# SimpleSwitchPirLightCO2_ESP03.net
KiCad netlist of a schematic drawn in EAGLE
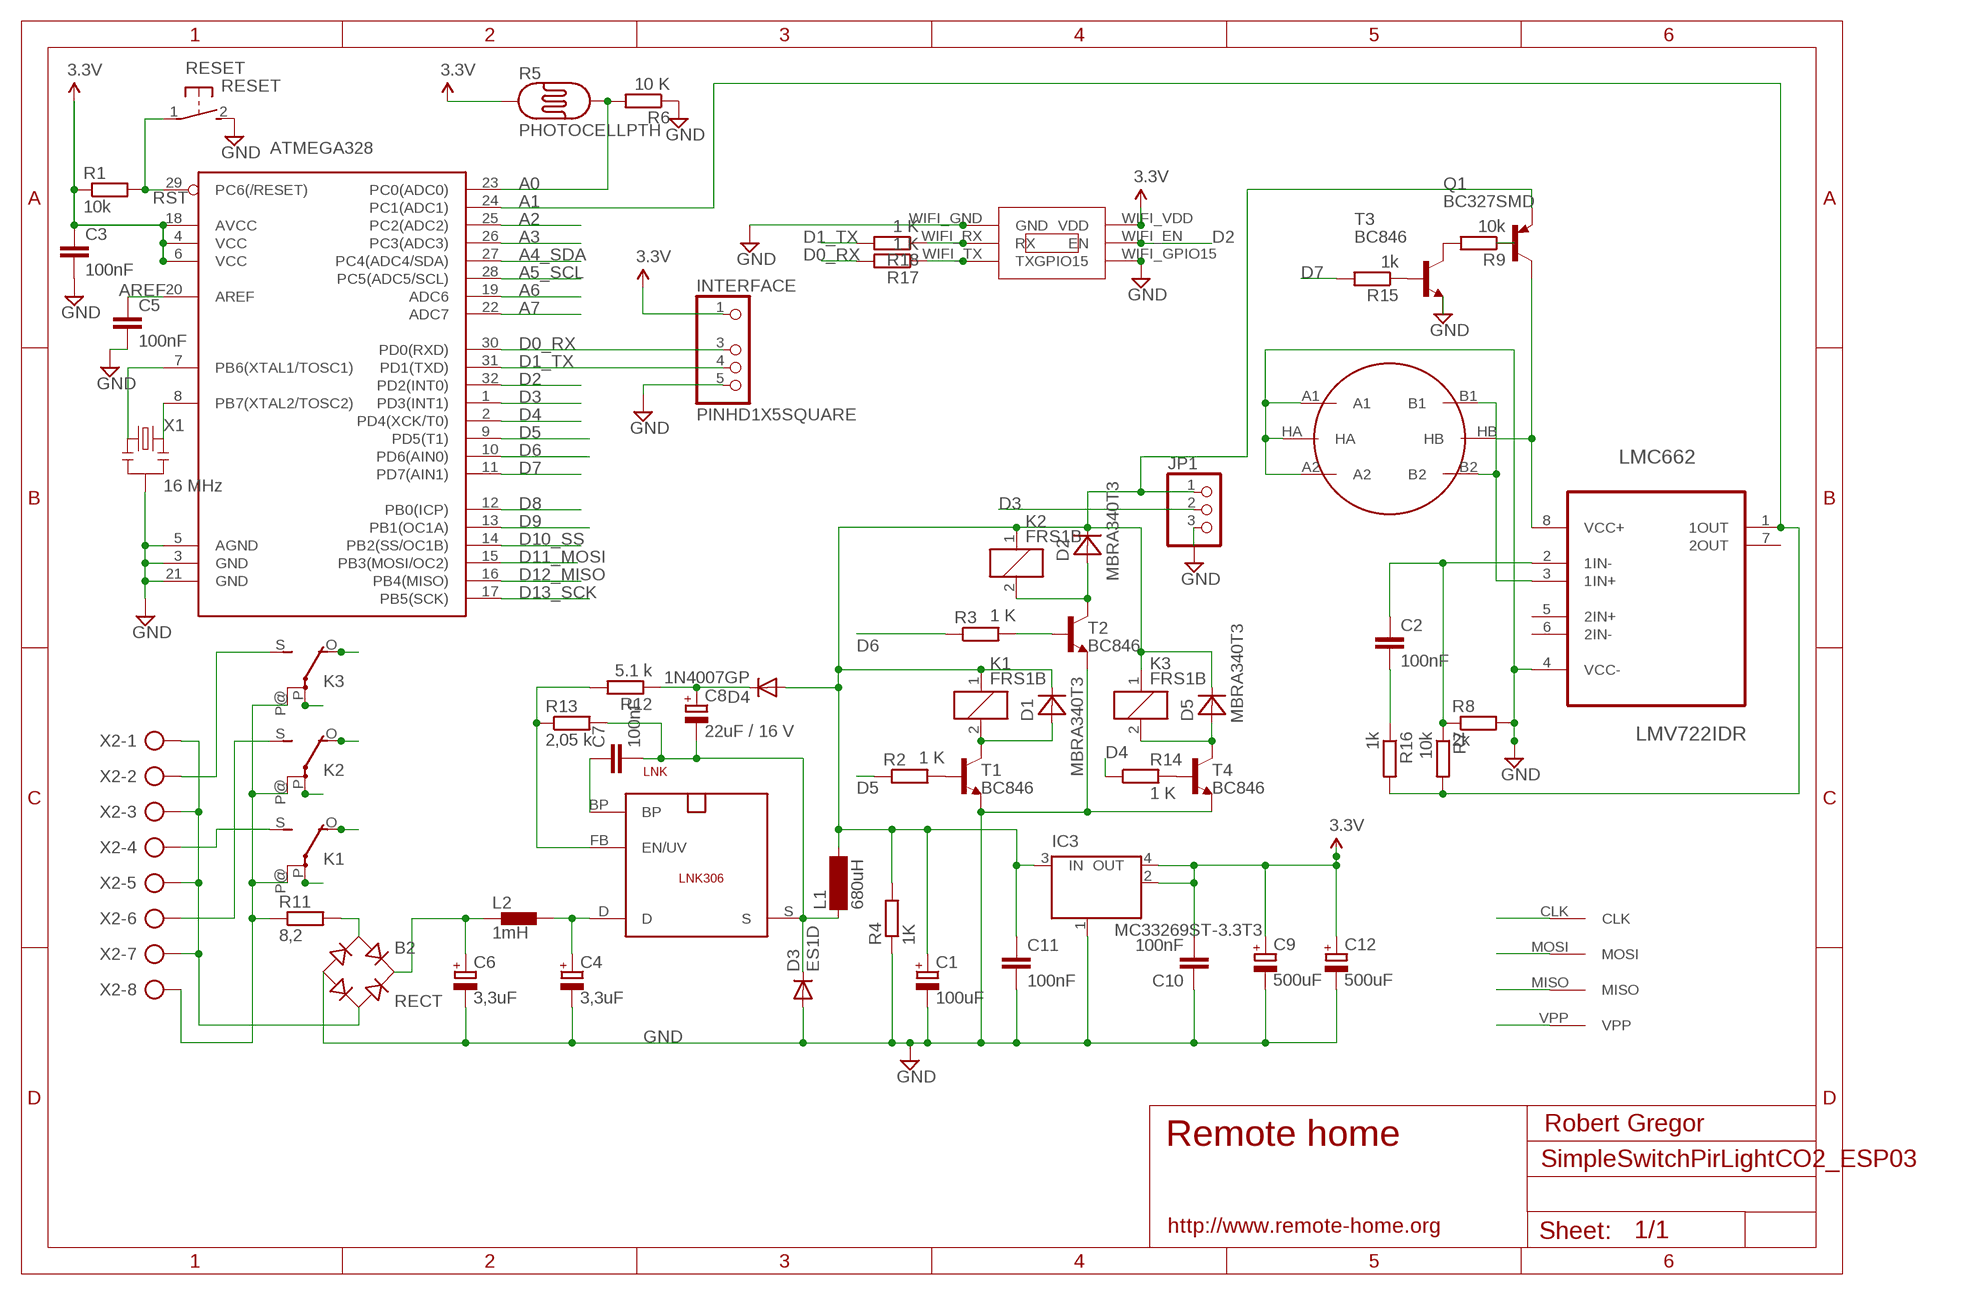
[diagram p0: schematic, sheet 1]

(export (version "E")
  (design (tool "Eeschema 10.0.6"))
  (components
    (comp (ref "ATMEGA328")
      (value "ATMega-328")
      (footprint "eagle-import:TQFP32-08")
      (libsource (lib "eagle-import") (part "ATMEGA168/328TQFP32"))
    )
    (comp (ref "B2")
      (value "RECT")
      (footprint "eagle-import:TO-269AA")
      (libsource (lib "eagle-import") (part "RECTIFIER-S40"))
    )
    (comp (ref "C1")
      (value "100uF")
      (footprint "eagle-import:SMC_B")
      (libsource (lib "eagle-import") (part "CPOL-EUSMCB"))
    )
    (comp (ref "C2")
      (value "100nF")
      (footprint "eagle-import:C2012")
      (libsource (lib "eagle-import") (part "C-EUC2012"))
    )
    (comp (ref "C3")
      (value "100nF")
      (footprint "eagle-import:C2012")
      (libsource (lib "eagle-import") (part "C-EUC2012"))
    )
    (comp (ref "C4")
      (value "3,3uF")
      (footprint "eagle-import:E5-10,5")
      (libsource (lib "eagle-import") (part "CPOL-EUE5-10.5"))
    )
    (comp (ref "C5")
      (value "100nF")
      (footprint "eagle-import:C2012")
      (libsource (lib "eagle-import") (part "C-EUC2012"))
    )
    (comp (ref "C6")
      (value "3,3uF")
      (footprint "eagle-import:E5-10,5")
      (libsource (lib "eagle-import") (part "CPOL-EUE5-10.5"))
    )
    (comp (ref "C7")
      (value "100nF")
      (footprint "eagle-import:C2012")
      (libsource (lib "eagle-import") (part "C-EUC2012"))
    )
    (comp (ref "C8")
      (value "22uF / 16 V")
      (footprint "eagle-import:SMC_C")
      (libsource (lib "eagle-import") (part "CPOL-EUSMCC"))
    )
    (comp (ref "C9")
      (value "500uF")
      (footprint "eagle-import:SMC_D")
      (libsource (lib "eagle-import") (part "CPOL-EUSMCD"))
    )
    (comp (ref "C10")
      (value "100nF")
      (footprint "eagle-import:C2012")
      (libsource (lib "eagle-import") (part "C-EUC2012"))
    )
    (comp (ref "C11")
      (value "100nF")
      (footprint "eagle-import:C2012")
      (libsource (lib "eagle-import") (part "C-EUC2012"))
    )
    (comp (ref "C12")
      (value "500uF")
      (footprint "eagle-import:SMC_D")
      (libsource (lib "eagle-import") (part "CPOL-EUSMCD"))
    )
    (comp (ref "D1")
      (value "MBRA340T3")
      (footprint "eagle-import:SMA")
      (libsource (lib "eagle-import") (part "MBRA340T3"))
    )
    (comp (ref "D2")
      (value "MBRA340T3")
      (footprint "eagle-import:SMA")
      (libsource (lib "eagle-import") (part "MBRA340T3"))
    )
    (comp (ref "D3")
      (value "ES1D")
      (footprint "eagle-import:DO214AC")
      (libsource (lib "eagle-import") (part "DIODE-DO214AC"))
    )
    (comp (ref "D4")
      (value "1N4007GP")
      (footprint "eagle-import:DO214AA")
      (libsource (lib "eagle-import") (part "DIODE-DO214AA"))
    )
    (comp (ref "D5")
      (value "MBRA340T3")
      (footprint "eagle-import:SMA")
      (libsource (lib "eagle-import") (part "MBRA340T3"))
    )
    (comp (ref "IC3")
      (value "MC33269ST-3.3T3")
      (footprint "eagle-import:SOT223")
      (libsource (lib "eagle-import") (part "MC33269ST-3.3T3"))
    )
    (comp (ref "INTERFACE")
      (value "PINHD1X5SQUARE")
      (footprint "eagle-import:PINHD1X05-SQUARE")
      (libsource (lib "eagle-import") (part "PINHD1X5SQUARE"))
    )
    (comp (ref "JP1")
      (value "PINHD-1X03_2.54-S")
      (footprint "eagle-import:1X03-S")
      (libsource (lib "eagle-import") (part "PINHD-1X03_2.54-S"))
    )
    (comp (ref "K1")
      (value "FRS1B")
      (footprint "eagle-import:FRS1B")
      (libsource (lib "eagle-import") (part "FRS1B"))
    )
    (comp (ref "K2")
      (value "FRS1B")
      (footprint "eagle-import:FRS1B")
      (libsource (lib "eagle-import") (part "FRS1B"))
    )
    (comp (ref "K3")
      (value "FRS1B")
      (footprint "eagle-import:FRS1B")
      (libsource (lib "eagle-import") (part "FRS1B"))
    )
    (comp (ref "L1")
      (value "680uH")
      (footprint "eagle-import:BS11")
      (libsource (lib "eagle-import") (part "BS11"))
    )
    (comp (ref "L2")
      (value "1mH")
      (footprint "eagle-import:BL02RN1")
      (libsource (lib "eagle-import") (part "BL02RN1"))
    )
    (comp (ref "LMC662")
      (value "LMV722IDR")
      (footprint "eagle-import:SOIC127P600X175-8N")
      (libsource (lib "eagle-import") (part "LMV722IDR"))
    )
    (comp (ref "LNK")
      (value "LNK306")
      (footprint "eagle-import:SO-8C")
      (libsource (lib "eagle-import") (part "SO-8C"))
    )
    (comp (ref "Q1")
      (value "BC327SMD")
      (footprint "eagle-import:SOT23-BEC")
      (libsource (lib "eagle-import") (part "BC327SMD"))
    )
    (comp (ref "R1")
      (value "10k")
      (footprint "eagle-import:R2012")
      (libsource (lib "eagle-import") (part "R-EU_R2012"))
    )
    (comp (ref "R2")
      (value "1 K")
      (footprint "eagle-import:M2012")
      (libsource (lib "eagle-import") (part "R-EU_M2012"))
    )
    (comp (ref "R3")
      (value "1 K")
      (footprint "eagle-import:M2012")
      (libsource (lib "eagle-import") (part "R-EU_M2012"))
    )
    (comp (ref "R4")
      (value "1K")
      (footprint "eagle-import:M2012")
      (libsource (lib "eagle-import") (part "R-EU_M2012"))
    )
    (comp (ref "R5")
      (value "PHOTOCELLPTH")
      (footprint "eagle-import:PHOTOCELL")
      (libsource (lib "eagle-import") (part "PHOTOCELLPTH"))
    )
    (comp (ref "R6")
      (value "10 K")
      (footprint "eagle-import:M2012")
      (libsource (lib "eagle-import") (part "R-EU_M2012"))
    )
    (comp (ref "R7")
      (value "10k")
      (footprint "eagle-import:R2012")
      (libsource (lib "eagle-import") (part "R-EU_R2012"))
    )
    (comp (ref "R8")
      (value "2k")
      (footprint "eagle-import:R2012")
      (libsource (lib "eagle-import") (part "R-EU_R2012"))
    )
    (comp (ref "R9")
      (value "10k")
      (footprint "eagle-import:R2012")
      (libsource (lib "eagle-import") (part "R-EU_R2012"))
    )
    (comp (ref "R11")
      (value "8,2")
      (footprint "eagle-import:0411_12")
      (libsource (lib "eagle-import") (part "R-EU_0411/12"))
    )
    (comp (ref "R12")
      (value "5.1 k")
      (footprint "eagle-import:M2012")
      (libsource (lib "eagle-import") (part "R-EU_M2012"))
    )
    (comp (ref "R13")
      (value "2,05 k")
      (footprint "eagle-import:M2012")
      (libsource (lib "eagle-import") (part "R-EU_M2012"))
    )
    (comp (ref "R14")
      (value "1 K")
      (footprint "eagle-import:M2012")
      (libsource (lib "eagle-import") (part "R-EU_M2012"))
    )
    (comp (ref "R15")
      (value "1k")
      (footprint "eagle-import:R2012")
      (libsource (lib "eagle-import") (part "R-EU_R2012"))
    )
    (comp (ref "R16")
      (value "1k")
      (footprint "eagle-import:R2012")
      (libsource (lib "eagle-import") (part "R-EU_R2012"))
    )
    (comp (ref "R17")
      (value "1 K")
      (footprint "eagle-import:M2012")
      (libsource (lib "eagle-import") (part "R-EU_M2012"))
    )
    (comp (ref "R18")
      (value "1 K")
      (footprint "eagle-import:M2012")
      (libsource (lib "eagle-import") (part "R-EU_M2012"))
    )
    (comp (ref "RESET")
      (value "RESET")
      (footprint "eagle-import:DTSM-3")
      (libsource (lib "eagle-import") (part "DTSM-3"))
    )
    (comp (ref "T1")
      (value "BC846")
      (footprint "eagle-import:SOT23")
      (libsource (lib "eagle-import") (part "BC846"))
    )
    (comp (ref "T2")
      (value "BC846")
      (footprint "eagle-import:SOT23")
      (libsource (lib "eagle-import") (part "BC846"))
    )
    (comp (ref "T3")
      (value "BC846")
      (footprint "eagle-import:SOT23")
      (libsource (lib "eagle-import") (part "BC846"))
    )
    (comp (ref "T4")
      (value "BC846")
      (footprint "eagle-import:SOT23")
      (libsource (lib "eagle-import") (part "BC846"))
    )
    (comp (ref "U$2")
      (value "AVRHEADERDIP")
      (footprint "eagle-import:AVRHEADER")
      (libsource (lib "eagle-import") (part "AVRHEADERDIP"))
    )
    (comp (ref "U$4")
      (value "METHANE_SENSOR")
      (footprint "eagle-import:MQ-3")
      (libsource (lib "eagle-import") (part "METHANE_SENSOR"))
    )
    (comp (ref "U$5")
      (value "ESP03")
      (footprint "eagle-import:ESP03")
      (libsource (lib "eagle-import") (part "ESP03"))
    )
    (comp (ref "X1")
      (value "16 MHz")
      (footprint "eagle-import:RESONATOR-SMD")
      (libsource (lib "eagle-import") (part "RESONATORSMD"))
    )
    (comp (ref "X2")
      (value "AK500/8")
      (footprint "eagle-import:AK500_8")
      (libsource (lib "eagle-import") (part "AK500/8"))
    )
  )
  (nets
    (net (code "1") (name "/A0") (class "Default")
      (node (ref "ATMEGA328") (pin "23") (pinfunction "PC0(ADC0)_23") (pintype "bidirectional"))
      (node (ref "R5") (pin "2") (pinfunction "P$2_2") (pintype "bidirectional"))
      (node (ref "R6") (pin "2") (pinfunction "2_2") (pintype "passive"))
    )
    (net (code "2") (name "/A1") (class "Default")
      (node (ref "ATMEGA328") (pin "24") (pinfunction "PC1(ADC1)_24") (pintype "bidirectional"))
      (node (ref "LMC662") (pin "1") (pinfunction "1OUT_1") (pintype "output"))
      (node (ref "R16") (pin "2") (pinfunction "2_2") (pintype "passive"))
      (node (ref "R7") (pin "2") (pinfunction "2_2") (pintype "passive"))
    )
    (net (code "3") (name "/A2") (class "Default")
      (node (ref "ATMEGA328") (pin "25") (pinfunction "PC2(ADC2)_25") (pintype "bidirectional"))
    )
    (net (code "4") (name "/A3") (class "Default")
      (node (ref "ATMEGA328") (pin "26") (pinfunction "PC3(ADC3)_26") (pintype "bidirectional"))
    )
    (net (code "5") (name "/A4_SDA") (class "Default")
      (node (ref "ATMEGA328") (pin "27") (pinfunction "PC4(ADC4/SDA)_27") (pintype "bidirectional"))
    )
    (net (code "6") (name "/A5_SCL") (class "Default")
      (node (ref "ATMEGA328") (pin "28") (pinfunction "PC5(ADC5/SCL)_28") (pintype "bidirectional"))
    )
    (net (code "7") (name "/A6") (class "Default")
      (node (ref "ATMEGA328") (pin "19") (pinfunction "ADC6_19") (pintype "bidirectional"))
    )
    (net (code "8") (name "/A7") (class "Default")
      (node (ref "ATMEGA328") (pin "22") (pinfunction "ADC7_22") (pintype "bidirectional"))
    )
    (net (code "9") (name "/AREF") (class "Default")
      (node (ref "ATMEGA328") (pin "20") (pinfunction "AREF_20") (pintype "bidirectional"))
      (node (ref "C5") (pin "1") (pinfunction "1_1") (pintype "passive"))
    )
    (net (code "10") (name "/D0_RX") (class "Default")
      (node (ref "ATMEGA328") (pin "30") (pinfunction "PD0(RXD)_30") (pintype "bidirectional"))
      (node (ref "INTERFACE") (pin "3") (pinfunction "3_3") (pintype "passive"))
      (node (ref "R17") (pin "2") (pinfunction "2_2") (pintype "passive"))
    )
    (net (code "11") (name "/D1_TX") (class "Default")
      (node (ref "ATMEGA328") (pin "31") (pinfunction "PD1(TXD)_31") (pintype "bidirectional"))
      (node (ref "INTERFACE") (pin "4") (pinfunction "4_4") (pintype "passive"))
      (node (ref "R18") (pin "2") (pinfunction "2_2") (pintype "passive"))
    )
    (net (code "12") (name "/D2") (class "Default")
      (node (ref "ATMEGA328") (pin "32") (pinfunction "PD2(INT0)_32") (pintype "bidirectional"))
      (node (ref "U$5") (pin "WIFI_EN") (pinfunction "EN_WIFI_EN") (pintype "input"))
    )
    (net (code "13") (name "/D3") (class "Default")
      (node (ref "ATMEGA328") (pin "1") (pinfunction "PD3(INT1)_1") (pintype "bidirectional"))
      (node (ref "JP1") (pin "2") (pinfunction "2_2") (pintype "passive"))
    )
    (net (code "14") (name "/D4") (class "Default")
      (node (ref "ATMEGA328") (pin "2") (pinfunction "PD4(XCK/T0)_2") (pintype "bidirectional"))
      (node (ref "R14") (pin "1") (pinfunction "1_1") (pintype "passive"))
    )
    (net (code "15") (name "/D5") (class "Default")
      (node (ref "ATMEGA328") (pin "9") (pinfunction "PD5(T1)_9") (pintype "bidirectional"))
      (node (ref "R2") (pin "1") (pinfunction "1_1") (pintype "passive"))
    )
    (net (code "16") (name "/D6") (class "Default")
      (node (ref "ATMEGA328") (pin "10") (pinfunction "PD6(AIN0)_10") (pintype "bidirectional"))
      (node (ref "R3") (pin "1") (pinfunction "1_1") (pintype "passive"))
    )
    (net (code "17") (name "/D7") (class "Default")
      (node (ref "ATMEGA328") (pin "11") (pinfunction "PD7(AIN1)_11") (pintype "bidirectional"))
      (node (ref "R15") (pin "2") (pinfunction "2_2") (pintype "passive"))
    )
    (net (code "18") (name "/D8") (class "Default")
      (node (ref "ATMEGA328") (pin "12") (pinfunction "PB0(ICP)_12") (pintype "bidirectional"))
    )
    (net (code "19") (name "/D9") (class "Default")
      (node (ref "ATMEGA328") (pin "13") (pinfunction "PB1(OC1A)_13") (pintype "bidirectional"))
    )
    (net (code "20") (name "/D10_SS") (class "Default")
      (node (ref "ATMEGA328") (pin "14") (pinfunction "PB2(SS/OC1B)_14") (pintype "bidirectional"))
    )
    (net (code "21") (name "/D11_MOSI") (class "Default")
      (node (ref "ATMEGA328") (pin "15") (pinfunction "PB3(MOSI/OC2)_15") (pintype "bidirectional"))
      (node (ref "U$2") (pin "MOSI") (pinfunction "MOSI_MOSI") (pintype "bidirectional"))
    )
    (net (code "22") (name "/D12_MISO") (class "Default")
      (node (ref "ATMEGA328") (pin "16") (pinfunction "PB4(MISO)_16") (pintype "bidirectional"))
      (node (ref "U$2") (pin "MISO") (pinfunction "MISO_MISO") (pintype "bidirectional"))
    )
    (net (code "23") (name "/D13_SCK") (class "Default")
      (node (ref "ATMEGA328") (pin "17") (pinfunction "PB5(SCK)_17") (pintype "bidirectional"))
      (node (ref "U$2") (pin "CLK") (pinfunction "CLK_CLK") (pintype "bidirectional"))
    )
    (net (code "24") (name "/RST") (class "Default")
      (node (ref "ATMEGA328") (pin "29") (pinfunction "PC6(/RESET)_29") (pintype "bidirectional"))
      (node (ref "R1") (pin "2") (pinfunction "2_2") (pintype "passive"))
      (node (ref "RESET") (pin "1") (pinfunction "1_1") (pintype "passive"))
      (node (ref "U$2") (pin "VPP") (pinfunction "VPP_VPP") (pintype "bidirectional"))
    )
    (net (code "25") (name "3.3V") (class "Default")
      (node (ref "ATMEGA328") (pin "18") (pinfunction "AVCC_18") (pintype "bidirectional"))
      (node (ref "ATMEGA328") (pin "4") (pinfunction "VCC_4") (pintype "bidirectional"))
      (node (ref "ATMEGA328") (pin "6") (pinfunction "VCC_6") (pintype "bidirectional"))
      (node (ref "C10") (pin "2") (pinfunction "2_2") (pintype "passive"))
      (node (ref "C12") (pin "+") (pinfunction "+_+") (pintype "passive"))
      (node (ref "C3") (pin "1") (pinfunction "1_1") (pintype "passive"))
      (node (ref "C9") (pin "+") (pinfunction "+_+") (pintype "passive"))
      (node (ref "IC3") (pin "2") (pinfunction "OUT_2") (pintype "passive"))
      (node (ref "IC3") (pin "4") (pinfunction "OUT_4") (pintype "passive"))
      (node (ref "INTERFACE") (pin "1") (pinfunction "1_1") (pintype "passive"))
      (node (ref "R1") (pin "1") (pinfunction "1_1") (pintype "passive"))
      (node (ref "R5") (pin "1") (pinfunction "P$1_1") (pintype "bidirectional"))
      (node (ref "U$5") (pin "WIFI_VDD") (pinfunction "VDD_WIFI_VDD") (pintype "power_in"))
    )
    (net (code "26") (name "GND") (class "Default")
      (node (ref "ATMEGA328") (pin "21") (pinfunction "GND_21") (pintype "bidirectional"))
      (node (ref "ATMEGA328") (pin "3") (pinfunction "GND_3") (pintype "bidirectional"))
      (node (ref "ATMEGA328") (pin "5") (pinfunction "AGND_5") (pintype "bidirectional"))
      (node (ref "B2") (pin "-") (pinfunction "-_-") (pintype "passive"))
      (node (ref "C1") (pin "-") (pinfunction "-_-") (pintype "passive"))
      (node (ref "C10") (pin "1") (pinfunction "1_1") (pintype "passive"))
      (node (ref "C11") (pin "2") (pinfunction "2_2") (pintype "passive"))
      (node (ref "C12") (pin "-") (pinfunction "-_-") (pintype "passive"))
      (node (ref "C3") (pin "2") (pinfunction "2_2") (pintype "passive"))
      (node (ref "C4") (pin "-") (pinfunction "-_-") (pintype "passive"))
      (node (ref "C5") (pin "2") (pinfunction "2_2") (pintype "passive"))
      (node (ref "C6") (pin "-") (pinfunction "-_-") (pintype "passive"))
      (node (ref "C9") (pin "-") (pinfunction "-_-") (pintype "passive"))
      (node (ref "D3") (pin "A") (pinfunction "A_A") (pintype "passive"))
      (node (ref "IC3") (pin "1") (pinfunction "GND/ADJ_1") (pintype "input"))
      (node (ref "INTERFACE") (pin "5") (pinfunction "5_5") (pintype "passive"))
      (node (ref "JP1") (pin "3") (pinfunction "3_3") (pintype "passive"))
      (node (ref "LMC662") (pin "4") (pinfunction "VCC-_4") (pintype "power_in"))
      (node (ref "R4") (pin "1") (pinfunction "1_1") (pintype "passive"))
      (node (ref "R6") (pin "1") (pinfunction "1_1") (pintype "passive"))
      (node (ref "R8") (pin "2") (pinfunction "2_2") (pintype "passive"))
      (node (ref "RESET") (pin "2") (pinfunction "2_2") (pintype "passive"))
      (node (ref "T1") (pin "2") (pinfunction "E_2") (pintype "passive"))
      (node (ref "T2") (pin "2") (pinfunction "E_2") (pintype "passive"))
      (node (ref "T3") (pin "2") (pinfunction "E_2") (pintype "passive"))
      (node (ref "T4") (pin "2") (pinfunction "E_2") (pintype "passive"))
      (node (ref "U$4") (pin "A1") (pinfunction "A1_A1") (pintype "bidirectional"))
      (node (ref "U$4") (pin "A2") (pinfunction "A2_A2") (pintype "bidirectional"))
      (node (ref "U$4") (pin "HA") (pinfunction "HA_HA") (pintype "bidirectional"))
      (node (ref "U$5") (pin "WIFI_GND") (pinfunction "GND_WIFI_GND") (pintype "power_in"))
      (node (ref "U$5") (pin "WIFI_GPIO15") (pinfunction "GPIO15_WIFI_GPIO15") (pintype "input"))
      (node (ref "X1") (pin "2") (pinfunction "2_2") (pintype "passive"))
    )
    (net (code "27") (name "Net-(ATMEGA328-PB6(XTAL1{slash}TOSC1))") (class "Default")
      (node (ref "ATMEGA328") (pin "7") (pinfunction "PB6(XTAL1/TOSC1)_7") (pintype "bidirectional"))
      (node (ref "X1") (pin "1") (pinfunction "1_1") (pintype "passive"))
    )
    (net (code "28") (name "Net-(ATMEGA328-PB7(XTAL2{slash}TOSC2))") (class "Default")
      (node (ref "ATMEGA328") (pin "8") (pinfunction "PB7(XTAL2/TOSC2)_8") (pintype "bidirectional"))
      (node (ref "X1") (pin "3") (pinfunction "3_3") (pintype "passive"))
    )
    (net (code "29") (name "Net-(B2-Pad+)") (class "Default")
      (node (ref "B2") (pin "+") (pinfunction "+_+") (pintype "passive"))
      (node (ref "C6") (pin "+") (pinfunction "+_+") (pintype "passive"))
      (node (ref "L2") (pin "1") (pinfunction "1_1") (pintype "passive"))
    )
    (net (code "30") (name "Net-(B2-PadAC1)") (class "Default")
      (node (ref "B2") (pin "AC1") (pinfunction "AC1_AC1") (pintype "passive"))
      (node (ref "R11") (pin "2") (pinfunction "2_2") (pintype "passive"))
    )
    (net (code "31") (name "Net-(C2-Pad2)") (class "Default")
      (node (ref "C2") (pin "2") (pinfunction "2_2") (pintype "passive"))
      (node (ref "R16") (pin "1") (pinfunction "1_1") (pintype "passive"))
    )
    (net (code "32") (name "Net-(C4-Pad+)") (class "Default")
      (node (ref "C4") (pin "+") (pinfunction "+_+") (pintype "passive"))
      (node (ref "L2") (pin "2") (pinfunction "2_2") (pintype "passive"))
      (node (ref "LNK") (pin "D") (pinfunction "D_D") (pintype "open_collector"))
    )
    (net (code "33") (name "Net-(C7-Pad1)") (class "Default")
      (node (ref "C7") (pin "1") (pinfunction "1_1") (pintype "passive"))
      (node (ref "LNK") (pin "BP") (pinfunction "BP_BP") (pintype "passive"))
    )
    (net (code "34") (name "Net-(C7-Pad2)") (class "Default")
      (node (ref "C7") (pin "2") (pinfunction "2_2") (pintype "passive"))
      (node (ref "C8") (pin "-") (pinfunction "-_-") (pintype "passive"))
      (node (ref "D3") (pin "C") (pinfunction "C_C") (pintype "passive"))
      (node (ref "L1") (pin "1") (pinfunction "1_1") (pintype "passive"))
      (node (ref "LNK") (pin "S") (pinfunction "S_S") (pintype "power_in"))
      (node (ref "R13") (pin "2") (pinfunction "2_2") (pintype "passive"))
    )
    (net (code "35") (name "Net-(C8-Pad+)") (class "Default")
      (node (ref "C8") (pin "+") (pinfunction "+_+") (pintype "passive"))
      (node (ref "D4") (pin "C") (pinfunction "C_C") (pintype "passive"))
      (node (ref "R12") (pin "1") (pinfunction "1_1") (pintype "passive"))
    )
    (net (code "36") (name "Net-(IC3-IN)") (class "Default")
      (node (ref "C1") (pin "+") (pinfunction "+_+") (pintype "passive"))
      (node (ref "C11") (pin "1") (pinfunction "1_1") (pintype "passive"))
      (node (ref "D1") (pin "C") (pinfunction "C_C") (pintype "passive"))
      (node (ref "D2") (pin "C") (pinfunction "C_C") (pintype "passive"))
      (node (ref "D4") (pin "A") (pinfunction "A_A") (pintype "passive"))
      (node (ref "D5") (pin "C") (pinfunction "C_C") (pintype "passive"))
      (node (ref "IC3") (pin "3") (pinfunction "IN_3") (pintype "input"))
      (node (ref "JP1") (pin "1") (pinfunction "1_1") (pintype "passive"))
      (node (ref "K1") (pin "1") (pinfunction "1_1") (pintype "passive"))
      (node (ref "K2") (pin "1") (pinfunction "1_1") (pintype "passive"))
      (node (ref "K3") (pin "1") (pinfunction "1_1") (pintype "passive"))
      (node (ref "L1") (pin "2") (pinfunction "2_2") (pintype "passive"))
      (node (ref "Q1") (pin "E") (pinfunction "E_E") (pintype "passive"))
      (node (ref "R4") (pin "2") (pinfunction "2_2") (pintype "passive"))
    )
    (net (code "37") (name "Net-(LMC662-1IN+)") (class "Default")
      (node (ref "LMC662") (pin "3") (pinfunction "1IN+_3") (pintype "input"))
      (node (ref "U$4") (pin "B1") (pinfunction "B1_B1") (pintype "bidirectional"))
      (node (ref "U$4") (pin "B2") (pinfunction "B2_B2") (pintype "bidirectional"))
    )
    (net (code "38") (name "Net-(LMC662-1IN-)") (class "Default")
      (node (ref "C2") (pin "1") (pinfunction "1_1") (pintype "passive"))
      (node (ref "LMC662") (pin "2") (pinfunction "1IN-_2") (pintype "input"))
      (node (ref "R7") (pin "1") (pinfunction "1_1") (pintype "passive"))
      (node (ref "R8") (pin "1") (pinfunction "1_1") (pintype "passive"))
    )
    (net (code "39") (name "Net-(LMC662-VCC+)") (class "Default")
      (node (ref "LMC662") (pin "8") (pinfunction "VCC+_8") (pintype "power_in"))
      (node (ref "Q1") (pin "C") (pinfunction "C_C") (pintype "passive"))
      (node (ref "U$4") (pin "HB") (pinfunction "HB_HB") (pintype "bidirectional"))
    )
    (net (code "40") (name "Net-(LNK-EN{slash}UV)") (class "Default")
      (node (ref "LNK") (pin "FB") (pinfunction "EN/UV_FB") (pintype "input"))
      (node (ref "R12") (pin "2") (pinfunction "2_2") (pintype "passive"))
      (node (ref "R13") (pin "1") (pinfunction "1_1") (pintype "passive"))
    )
    (net (code "41") (name "Net-(Q1-PadB)") (class "Default")
      (node (ref "Q1") (pin "B") (pinfunction "B_B") (pintype "passive"))
      (node (ref "R9") (pin "1") (pinfunction "1_1") (pintype "passive"))
    )
    (net (code "42") (name "Net-(T1-B)") (class "Default")
      (node (ref "R2") (pin "2") (pinfunction "2_2") (pintype "passive"))
      (node (ref "T1") (pin "1") (pinfunction "B_1") (pintype "passive"))
    )
    (net (code "43") (name "Net-(T1-C)") (class "Default")
      (node (ref "D1") (pin "A") (pinfunction "A_A") (pintype "passive"))
      (node (ref "K1") (pin "2") (pinfunction "2_2") (pintype "passive"))
      (node (ref "T1") (pin "3") (pinfunction "C_3") (pintype "passive"))
    )
    (net (code "44") (name "Net-(T2-B)") (class "Default")
      (node (ref "R3") (pin "2") (pinfunction "2_2") (pintype "passive"))
      (node (ref "T2") (pin "1") (pinfunction "B_1") (pintype "passive"))
    )
    (net (code "45") (name "Net-(T2-C)") (class "Default")
      (node (ref "D2") (pin "A") (pinfunction "A_A") (pintype "passive"))
      (node (ref "K2") (pin "2") (pinfunction "2_2") (pintype "passive"))
      (node (ref "T2") (pin "3") (pinfunction "C_3") (pintype "passive"))
    )
    (net (code "46") (name "Net-(T3-B)") (class "Default")
      (node (ref "R15") (pin "1") (pinfunction "1_1") (pintype "passive"))
      (node (ref "T3") (pin "1") (pinfunction "B_1") (pintype "passive"))
    )
    (net (code "47") (name "Net-(T3-C)") (class "Default")
      (node (ref "R9") (pin "2") (pinfunction "2_2") (pintype "passive"))
      (node (ref "T3") (pin "3") (pinfunction "C_3") (pintype "passive"))
    )
    (net (code "48") (name "Net-(T4-B)") (class "Default")
      (node (ref "R14") (pin "2") (pinfunction "2_2") (pintype "passive"))
      (node (ref "T4") (pin "1") (pinfunction "B_1") (pintype "passive"))
    )
    (net (code "49") (name "Net-(T4-C)") (class "Default")
      (node (ref "D5") (pin "A") (pinfunction "A_A") (pintype "passive"))
      (node (ref "K3") (pin "2") (pinfunction "2_2") (pintype "passive"))
      (node (ref "T4") (pin "3") (pinfunction "C_3") (pintype "passive"))
    )
    (net (code "50") (name "Net-(U$5-RX)") (class "Default")
      (node (ref "R18") (pin "1") (pinfunction "1_1") (pintype "passive"))
      (node (ref "U$5") (pin "WIFI_RX") (pinfunction "RX_WIFI_RX") (pintype "input"))
    )
    (net (code "51") (name "Net-(U$5-TX)") (class "Default")
      (node (ref "R17") (pin "1") (pinfunction "1_1") (pintype "passive"))
      (node (ref "U$5") (pin "WIFI_TX") (pinfunction "TX_WIFI_TX") (pintype "output"))
    )
    (net (code "52") (name "Net-(X2A-KL)") (class "Default")
      (node (ref "B2") (pin "AC2") (pinfunction "AC2_AC2") (pintype "passive"))
      (node (ref "X2") (pin "1") (pinfunction "KL_1") (pintype "passive"))
      (node (ref "X2") (pin "3") (pinfunction "KL_3") (pintype "passive"))
      (node (ref "X2") (pin "5") (pinfunction "KL_5") (pintype "passive"))
      (node (ref "X2") (pin "7") (pinfunction "KL_7") (pintype "passive"))
    )
    (net (code "53") (name "Net-(X2B-KL)") (class "Default")
      (node (ref "K3") (pin "S") (pinfunction "S_S") (pintype "passive"))
      (node (ref "X2") (pin "2") (pinfunction "KL_2") (pintype "passive"))
    )
    (net (code "54") (name "Net-(X2D-KL)") (class "Default")
      (node (ref "K1") (pin "S") (pinfunction "S_S") (pintype "passive"))
      (node (ref "X2") (pin "4") (pinfunction "KL_4") (pintype "passive"))
    )
    (net (code "55") (name "Net-(X2F-KL)") (class "Default")
      (node (ref "K2") (pin "S") (pinfunction "S_S") (pintype "passive"))
      (node (ref "X2") (pin "6") (pinfunction "KL_6") (pintype "passive"))
    )
    (net (code "56") (name "Net-(X2H-KL)") (class "Default")
      (node (ref "K1") (pin "P@") (pinfunction "P_P@") (pintype "passive"))
      (node (ref "K2") (pin "P@") (pinfunction "P_P@") (pintype "passive"))
      (node (ref "K3") (pin "P@") (pinfunction "P_P@") (pintype "passive"))
      (node (ref "R11") (pin "1") (pinfunction "1_1") (pintype "passive"))
      (node (ref "X2") (pin "8") (pinfunction "KL_8") (pintype "passive"))
    )
    (net (code "57") (name "unconnected-(K1-PadO)") (class "Default")
      (node (ref "K1") (pin "O") (pinfunction "O_O") (pintype "passive"))
    )
    (net (code "58") (name "unconnected-(K1-PadP)") (class "Default")
      (node (ref "K1") (pin "P") (pinfunction "P_P") (pintype "passive"))
    )
    (net (code "59") (name "unconnected-(K2-PadO)") (class "Default")
      (node (ref "K2") (pin "O") (pinfunction "O_O") (pintype "passive"))
    )
    (net (code "60") (name "unconnected-(K2-PadP)") (class "Default")
      (node (ref "K2") (pin "P") (pinfunction "P_P") (pintype "passive"))
    )
    (net (code "61") (name "unconnected-(K3-PadO)") (class "Default")
      (node (ref "K3") (pin "O") (pinfunction "O_O") (pintype "passive"))
    )
    (net (code "62") (name "unconnected-(K3-PadP)") (class "Default")
      (node (ref "K3") (pin "P") (pinfunction "P_P") (pintype "passive"))
    )
    (net (code "63") (name "unconnected-(LMC662-2IN+-Pad5)") (class "Default")
      (node (ref "LMC662") (pin "5") (pinfunction "2IN+_5") (pintype "input"))
    )
    (net (code "64") (name "unconnected-(LMC662-2IN--Pad6)") (class "Default")
      (node (ref "LMC662") (pin "6") (pinfunction "2IN-_6") (pintype "input"))
    )
    (net (code "65") (name "unconnected-(LMC662-2OUT-Pad7)") (class "Default")
      (node (ref "LMC662") (pin "7") (pinfunction "2OUT_7") (pintype "output"))
    )
  )
)
